# Photocoupler12Vinput.net
KiCad netlist of a schematic drawn in Altium Designer
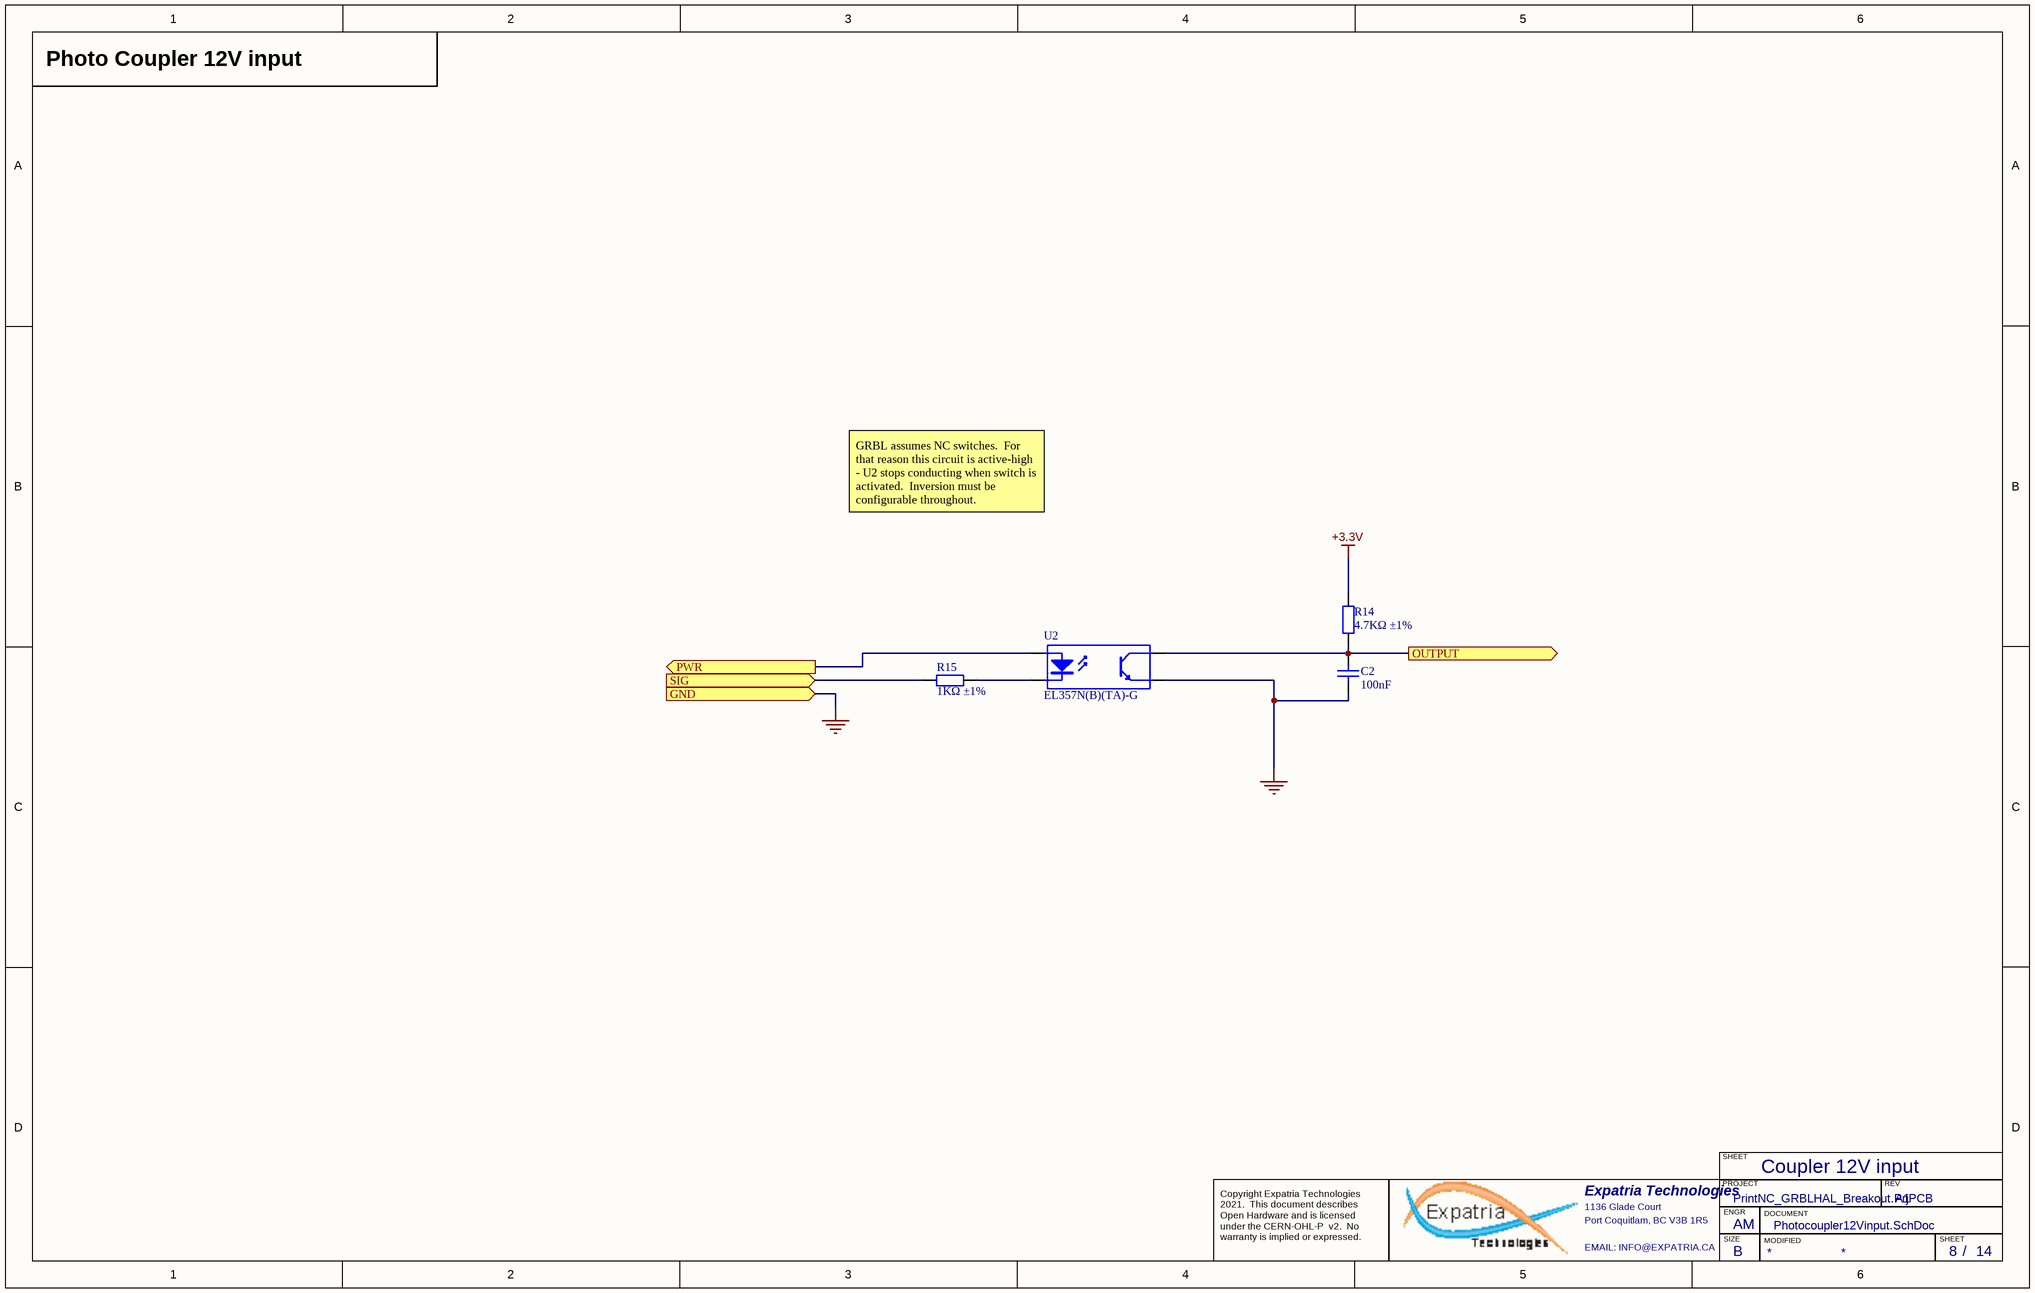
[diagram p0: Photocoupler12Vinput.SchDoc]

(export (version "E")
  (design (tool "Eeschema 10.0.6"))
  (components
    (comp (ref "C2")
      (value "100nF")
      (footprint "0402_C")
      (description "Chip capacitors")
      (fields
        (field (name "MANUFACTURER") "Samsung Electro-Mechanics")
        (field (name "PARTNUMBER") "CL05B104KO5NNNC")
      )
      (libsource (lib "Cap") (part "0402 100nF (104) 10% 16V"))
    )
    (comp (ref "R14")
      (value "4.7KΩ ±1%")
      (footprint "0402_R")
      (description "Chip resistor")
      (fields (field (name "MANUFACTURER") "Uniroyal Elec") (field (name "PARTNUMBER") "0402WGF4701TCE"))
      (libsource (lib "PrintNC_GRBLHAL_Breakout") (part "0402 4.7K (4701) 1%"))
    )
    (comp (ref "R15")
      (value "1KΩ ±1%")
      (footprint "0402_R")
      (description "Chip resistor")
      (fields (field (name "MANUFACTURER") "Uniroyal Elec") (field (name "PARTNUMBER") "0402WGF1001TCE"))
      (libsource (lib "PrintNC_GRBLHAL_Breakout") (part "0402 1K (1001) 1%"))
    )
    (comp (ref "U2")
      (value "EL357N(B)(TA)-G")
      (footprint "SOP-4_P2.54")
      (description "贴片光耦")
      (libsource (lib "PrintNC_GRBLHAL_Breakout") (part "EL357N(B)(TA)-G_[C6649]"))
    )
  )
  (nets
    (net (code "1") (name "+3.3V") (class "Default")
      (node (ref "R14") (pin "2") (pinfunction "2_2") (pintype "passive"))
    )
    (net (code "2") (name "/OUTPUT") (class "Default")
      (node (ref "C2") (pin "2") (pinfunction "2_2") (pintype "passive"))
      (node (ref "R14") (pin "1") (pinfunction "1_1") (pintype "passive"))
      (node (ref "U2") (pin "4") (pinfunction "C_4") (pintype "passive"))
    )
    (net (code "3") (name "/PWR") (class "Default")
      (node (ref "U2") (pin "1") (pinfunction "A_1") (pintype "passive"))
    )
    (net (code "4") (name "/SIG") (class "Default")
      (node (ref "R15") (pin "1") (pinfunction "1_1") (pintype "passive"))
    )
    (net (code "5") (name "GND") (class "Default")
      (node (ref "C2") (pin "1") (pinfunction "1_1") (pintype "passive"))
      (node (ref "U2") (pin "3") (pinfunction "E_3") (pintype "passive"))
    )
    (net (code "6") (name "Net-(U2-K)") (class "Default")
      (node (ref "R15") (pin "2") (pinfunction "2_2") (pintype "passive"))
      (node (ref "U2") (pin "2") (pinfunction "K_2") (pintype "passive"))
    )
  )
)
